# dip_s9032-02.net
KiCad netlist of a schematic drawn in EAGLE
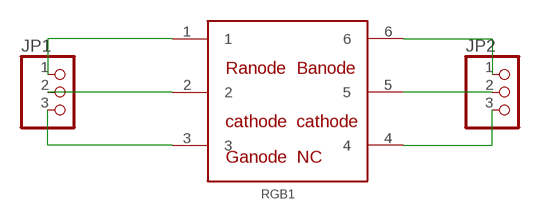
[diagram p0: schematic, sheet 1]

(export (version "E")
  (design (tool "Eeschema 10.0.6"))
  (components
    (comp (ref "JP1")
      (value "PINHD-1X3")
      (footprint "eagle-import:1X03")
      (libsource (lib "eagle-import") (part "PINHD-1X3"))
    )
    (comp (ref "JP2")
      (value "PINHD-1X3")
      (footprint "eagle-import:1X03")
      (libsource (lib "eagle-import") (part "PINHD-1X3"))
    )
    (comp (ref "RGB1")
      (value "S9032-02")
      (footprint "eagle-import:RGB_SENSOR")
      (libsource (lib "eagle-import") (part "S9032-02"))
    )
  )
  (nets
    (net (code "1") (name "Net-(JP1-Pad1)") (class "Default")
      (node (ref "JP1") (pin "1") (pinfunction "1_1") (pintype "passive"))
      (node (ref "RGB1") (pin "1") (pinfunction "1_1") (pintype "bidirectional"))
    )
    (net (code "2") (name "Net-(JP1-Pad2)") (class "Default")
      (node (ref "JP1") (pin "2") (pinfunction "2_2") (pintype "passive"))
      (node (ref "RGB1") (pin "2") (pinfunction "2_2") (pintype "bidirectional"))
    )
    (net (code "3") (name "Net-(JP1-Pad3)") (class "Default")
      (node (ref "JP1") (pin "3") (pinfunction "3_3") (pintype "passive"))
      (node (ref "RGB1") (pin "3") (pinfunction "3_3") (pintype "bidirectional"))
    )
    (net (code "4") (name "Net-(JP2-Pad1)") (class "Default")
      (node (ref "JP2") (pin "1") (pinfunction "1_1") (pintype "passive"))
      (node (ref "RGB1") (pin "6") (pinfunction "6_6") (pintype "bidirectional"))
    )
    (net (code "5") (name "Net-(JP2-Pad2)") (class "Default")
      (node (ref "JP2") (pin "2") (pinfunction "2_2") (pintype "passive"))
      (node (ref "RGB1") (pin "5") (pinfunction "5_5") (pintype "bidirectional"))
    )
    (net (code "6") (name "Net-(JP2-Pad3)") (class "Default")
      (node (ref "JP2") (pin "3") (pinfunction "3_3") (pintype "passive"))
      (node (ref "RGB1") (pin "4") (pinfunction "4_4") (pintype "bidirectional"))
    )
  )
)
